# I2C_Display.net
KiCad netlist of a schematic drawn in Altium Designer
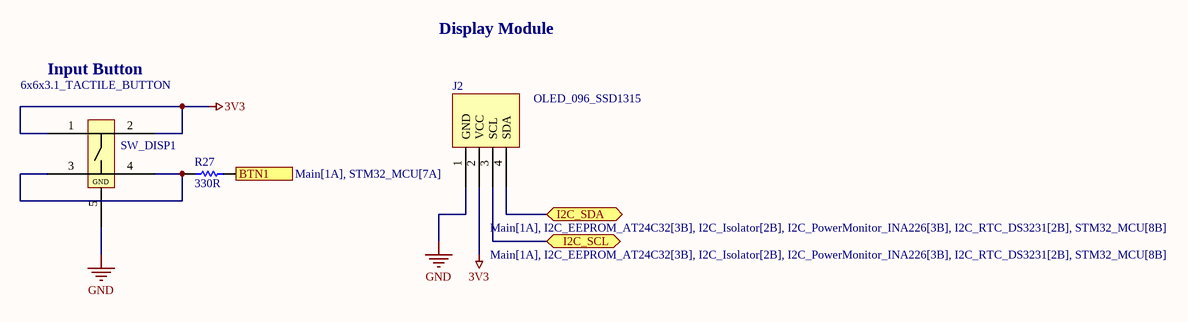
[diagram p0: I2C_Display.SchDoc]

(export (version "E")
  (design (tool "Eeschema 10.0.6"))
  (components
    (comp (ref "J2")
      (value "OLED_096_SSD1315")
      (footprint "OLED_096_SSD1315")
      (libsource (lib "OLED_096_SSD1315") (part "OLED_096_SSD1315"))
    )
    (comp (ref "R27")
      (value "330R")
      (footprint "RESC1608X55X30LL15T15")
      (description "Chip Resistor, 330 Ohm, +/- 1%, 0.1 W, -55 to 155 degC, 0603 (1608 Metric), RoHS, Tape and Reel")
      (libsource (lib "Altium Content Vault") (part "RES-2"))
    )
    (comp (ref "SW_DISP1")
      (value "6x6x3.1_TACTILE_BUTTON")
      (footprint "6x6x3.1_TACTILE_BUTTON")
      (libsource (lib "6x6x3.1_TACTILE_BUTTON") (part "6x6x3.1_TACTILE_BUTTON"))
    )
  )
  (nets
    (net (code "1") (name "/BTN1") (class "Default")
      (node (ref "R27") (pin "2") (pinfunction "2_2") (pintype "passive"))
    )
    (net (code "2") (name "/I2C_SCL") (class "Default")
      (node (ref "J2") (pin "3") (pinfunction "SCL_3") (pintype "passive"))
    )
    (net (code "3") (name "/I2C_SDA") (class "Default")
      (node (ref "J2") (pin "4") (pinfunction "SDA_4") (pintype "passive"))
    )
    (net (code "4") (name "3V3") (class "Default")
      (node (ref "J2") (pin "2") (pinfunction "VCC_2") (pintype "passive"))
      (node (ref "SW_DISP1") (pin "1") (pinfunction "1_1") (pintype "passive"))
      (node (ref "SW_DISP1") (pin "2") (pinfunction "2_2") (pintype "passive"))
    )
    (net (code "5") (name "GND") (class "Default")
      (node (ref "J2") (pin "1") (pinfunction "GND_1") (pintype "passive"))
      (node (ref "SW_DISP1") (pin "5") (pintype "passive"))
    )
    (net (code "6") (name "Net-(R27-Pad1)") (class "Default")
      (node (ref "R27") (pin "1") (pinfunction "1_1") (pintype "passive"))
      (node (ref "SW_DISP1") (pin "3") (pinfunction "3_3") (pintype "passive"))
      (node (ref "SW_DISP1") (pin "4") (pinfunction "4_4") (pintype "passive"))
    )
  )
)
